# power_5V.net
KiCad netlist of a schematic drawn in Altium Designer
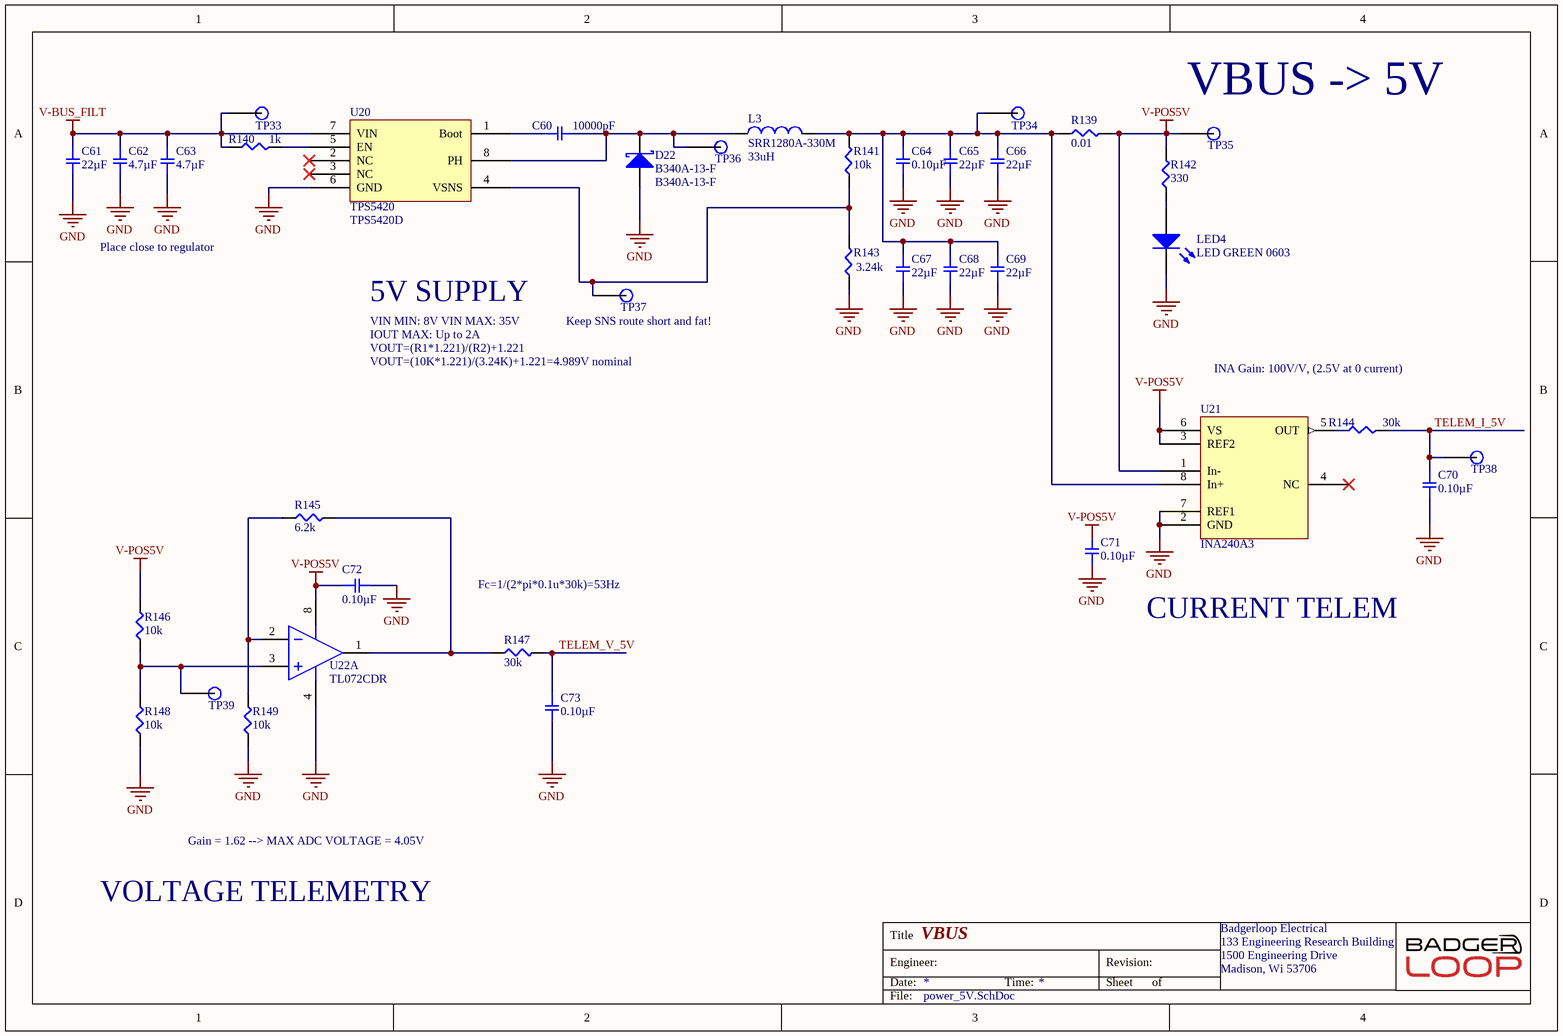
[diagram p0: power_5V.SchDoc]

(export (version "E")
  (design (tool "Eeschema 10.0.6"))
  (components
    (comp (ref "C60")
      (value "10000pF")
      (footprint "SMD-0805C")
      (description "CAP CER 10000PF 250V X7T 0805")
      (fields
        (field (name "DIGI-KEY PART NUMBER") "490-13986-1-ND")
        (field (name "PART NUMBER") "GC321AD72E103KX01D")
      )
      (libsource (lib "capacitors") (part "GC321AD72E103KX01D"))
    )
    (comp (ref "C61")
      (value "22µF")
      (footprint "SMD-1206C")
      (description "CAP CER 22UF 25V X5R 1206")
      (fields
        (field (name "DIGI-KEY PART NUMBER") "490-12451-1-ND")
        (field (name "PART NUMBER") "GRT31CR61E226ME01L")
      )
      (libsource (lib "capacitors") (part "GRT31CR61E226ME01L"))
    )
    (comp (ref "C62")
      (value "4.7µF")
      (footprint "SMD-1206C")
      (description "CAP CER 4.7UF 50V X7S 1206")
      (fields
        (field (name "DIGI-KEY PART NUMBER") "490-11167-1-ND")
        (field (name "PART NUMBER") "GCM31CC71H475KA03L")
      )
      (libsource (lib "capacitors") (part "GCM31CC71H475KA03L"))
    )
    (comp (ref "C63")
      (value "4.7µF")
      (footprint "SMD-1206C")
      (description "CAP CER 4.7UF 50V X7S 1206")
      (fields
        (field (name "DIGI-KEY PART NUMBER") "490-11167-1-ND")
        (field (name "PART NUMBER") "GCM31CC71H475KA03L")
      )
      (libsource (lib "capacitors") (part "GCM31CC71H475KA03L"))
    )
    (comp (ref "C64")
      (value "0.10µF")
      (footprint "SMD-0805C")
      (description "CAP CER 0.1UF 10V U2J 0805")
      (fields
        (field (name "DIGI-KEY PART NUMBER") "490-11592-1-ND")
        (field (name "PART NUMBER") "GRM21B7U1A104JA01L")
      )
      (libsource (lib "capacitors") (part "GRM21B7U1A104JA01L"))
    )
    (comp (ref "C65")
      (value "22µF")
      (footprint "SMD-1206C")
      (description "CAP CER 22UF 25V X5R 1206")
      (fields
        (field (name "DIGI-KEY PART NUMBER") "490-12451-1-ND")
        (field (name "PART NUMBER") "GRT31CR61E226ME01L")
      )
      (libsource (lib "capacitors") (part "GRT31CR61E226ME01L"))
    )
    (comp (ref "C66")
      (value "22µF")
      (footprint "SMD-1206C")
      (description "CAP CER 22UF 25V X5R 1206")
      (fields
        (field (name "DIGI-KEY PART NUMBER") "490-12451-1-ND")
        (field (name "PART NUMBER") "GRT31CR61E226ME01L")
      )
      (libsource (lib "capacitors") (part "GRT31CR61E226ME01L"))
    )
    (comp (ref "C67")
      (value "22µF")
      (footprint "SMD-1206C")
      (description "CAP CER 22UF 25V X5R 1206")
      (fields
        (field (name "DIGI-KEY PART NUMBER") "490-12451-1-ND")
        (field (name "PART NUMBER") "GRT31CR61E226ME01L")
      )
      (libsource (lib "capacitors") (part "GRT31CR61E226ME01L"))
    )
    (comp (ref "C68")
      (value "22µF")
      (footprint "SMD-1206C")
      (description "CAP CER 22UF 25V X5R 1206")
      (fields
        (field (name "DIGI-KEY PART NUMBER") "490-12451-1-ND")
        (field (name "PART NUMBER") "GRT31CR61E226ME01L")
      )
      (libsource (lib "capacitors") (part "GRT31CR61E226ME01L"))
    )
    (comp (ref "C69")
      (value "22µF")
      (footprint "SMD-1206C")
      (description "CAP CER 22UF 25V X5R 1206")
      (fields
        (field (name "DIGI-KEY PART NUMBER") "490-12451-1-ND")
        (field (name "PART NUMBER") "GRT31CR61E226ME01L")
      )
      (libsource (lib "capacitors") (part "GRT31CR61E226ME01L"))
    )
    (comp (ref "C70")
      (value "0.10µF")
      (footprint "SMD-0805C")
      (description "CAP CER 0.1UF 16V X7R 0805")
      (fields
        (field (name "DIGI-KEY PART NUMBER") "490-1683-1-ND")
        (field (name "PART NUMBER") "GRM219R71C104KA01D")
      )
      (libsource (lib "capacitors") (part "GRM219R71C104KA01D"))
    )
    (comp (ref "C71")
      (value "0.10µF")
      (footprint "SMD-0805C")
      (description "CAP CER 0.1UF 10V U2J 0805")
      (fields
        (field (name "DIGI-KEY PART NUMBER") "490-11592-1-ND")
        (field (name "PART NUMBER") "GRM21B7U1A104JA01L")
      )
      (libsource (lib "capacitors") (part "GRM21B7U1A104JA01L"))
    )
    (comp (ref "C72")
      (value "0.10µF")
      (footprint "SMD-0805C")
      (description "CAP CER 0.1UF 10V U2J 0805")
      (fields
        (field (name "DIGI-KEY PART NUMBER") "490-11592-1-ND")
        (field (name "PART NUMBER") "GRM21B7U1A104JA01L")
      )
      (libsource (lib "capacitors") (part "GRM21B7U1A104JA01L"))
    )
    (comp (ref "C73")
      (value "0.10µF")
      (footprint "SMD-0805C")
      (description "CAP CER 0.1UF 16V X7R 0805")
      (fields
        (field (name "DIGI-KEY PART NUMBER") "490-1683-1-ND")
        (field (name "PART NUMBER") "GRM219R71C104KA01D")
      )
      (libsource (lib "capacitors") (part "GRM219R71C104KA01D"))
    )
    (comp (ref "D22")
      (value "B340A-13-F")
      (footprint "DIOM4326X20N")
      (description "DIODE SCHOTTKY 40V 3A SMA")
      (fields
        (field (name "MANUFACTURER") "Diodes")
        (field (name "VOLTAGE") "40V")
        (field (name "MANUFACTURER PART NUMBER") "B340A-13-F")
      )
      (libsource (lib "misc") (part "B340A-13-F"))
    )
    (comp (ref "L3")
      (value "SRR1280A-330M")
      (footprint "INDM120125X75N")
      (description "Inductor Power Shielded Wirewound 33uH 20% 1KHz 28Q-Factor Ferrite 3.5A 57mOhm DCR Automotive T/R")
      (fields
        (field (name "MANUFACTURER") "Bourns")
        (field (name "TOLERANCE") "20%")
        (field (name "INDUCTANCE") "33uH")
      )
      (libsource (lib "misc") (part "SRR1280A-330M"))
    )
    (comp (ref "LED4")
      (value "LED GREEN 0603")
      (footprint "LED 0603 GREEN")
      (fields (field (name "MANUFACTURER") "Lite-On Inc."))
      (libsource (lib "misc") (part "LED GREEN 0603"))
    )
    (comp (ref "R139")
      (value "0.01")
      (footprint "SMD-1206-RES")
      (description "RES SMD 0.01 OHM 1% 1/2W 1206")
      (fields
        (field (name "PART NUMBER") "ERJ-MP2KF10MU")
        (field (name "DIGI-KEY PART NUMBER") "P19322CT-ND")
      )
      (libsource (lib "resistors") (part "ERJ-MP2KF10MU"))
    )
    (comp (ref "R140")
      (value "1k")
      (footprint "SMD-0805-RES")
      (description "RES SMD 1K OHM 5% 1/2W 0805")
      (fields
        (field (name "PART NUMBER") "ERJ-P06J102V")
        (field (name "DIGI-KEY PART NUMBER") "P1.0KADCT-ND")
      )
      (libsource (lib "resistors") (part "ERJ-P06J102V"))
    )
    (comp (ref "R141")
      (value "10k")
      (footprint "SMD-0805-RES")
      (description "RES SMD 10K OHM 5% 1/2W 0805")
      (fields (field (name "PART NUMBER") "ERJ-P06J103V") (field (name "DIGI-KEY PART NUMBER") "P10KADCT-ND"))
      (libsource (lib "resistors") (part "ERJ-P06J103V"))
    )
    (comp (ref "R142")
      (value "330")
      (footprint "SMD-0805-RES")
      (description "RES SMD 330 OHM 5% 1/2W 0805")
      (fields (field (name "PART NUMBER") "ERJ-P06J331V") (field (name "DIGI-KEY PART NUMBER") "P330ADCT-ND"))
      (libsource (lib "resistors") (part "ERJ-P06J331V"))
    )
    (comp (ref "R143")
      (value "3.24k")
      (footprint "SMD-0805-RES")
      (description "RES SMD 3.24K OHM 1% 1/8W 0805")
      (fields
        (field (name "PART NUMBER") "ERJ-6ENF3241V")
        (field (name "DIGI-KEY PART NUMBER") "P3.24KCCT-ND")
      )
      (libsource (lib "resistors") (part "ERJ-6ENF3241V"))
    )
    (comp (ref "R144")
      (value "30k")
      (footprint "SMD-0805-RES")
      (description "RES SMD 30K OHM 1% 1/8W 0805")
      (fields
        (field (name "PART NUMBER") "ERJ-6ENF3002V")
        (field (name "DIGI-KEY PART NUMBER") "P30.0KCCT-ND")
      )
      (libsource (lib "resistors") (part "ERJ-6ENF3002V"))
    )
    (comp (ref "R145")
      (value "6.2k")
      (footprint "SMD-0805-RES")
      (description "RES SMD 6.2K OHM 5% 1/2W 0805")
      (fields
        (field (name "PART NUMBER") "ERJ-P06J622V")
        (field (name "DIGI-KEY PART NUMBER") "P6.2KADCT-ND")
      )
      (libsource (lib "resistors") (part "ERJ-P06J622V"))
    )
    (comp (ref "R146")
      (value "10k")
      (footprint "SMD-0805-RES")
      (description "RES SMD 10K OHM 5% 1/2W 0805")
      (fields (field (name "PART NUMBER") "ERJ-P06J103V") (field (name "DIGI-KEY PART NUMBER") "P10KADCT-ND"))
      (libsource (lib "resistors") (part "ERJ-P06J103V"))
    )
    (comp (ref "R147")
      (value "30k")
      (footprint "SMD-0805-RES")
      (description "RES SMD 30K OHM 5% 1/2W 0805")
      (fields (field (name "PART NUMBER") "ERJ-P06J303V") (field (name "DIGI-KEY PART NUMBER") "P30KADCT-ND"))
      (libsource (lib "resistors") (part "ERJ-P06J303V"))
    )
    (comp (ref "R148")
      (value "10k")
      (footprint "SMD-0805-RES")
      (description "RES SMD 10K OHM 5% 1/2W 0805")
      (fields (field (name "PART NUMBER") "ERJ-P06J103V") (field (name "DIGI-KEY PART NUMBER") "P10KADCT-ND"))
      (libsource (lib "resistors") (part "ERJ-P06J103V"))
    )
    (comp (ref "R149")
      (value "10k")
      (footprint "SMD-0805-RES")
      (description "RES SMD 10K OHM 5% 1/2W 0805")
      (fields (field (name "PART NUMBER") "ERJ-P06J103V") (field (name "DIGI-KEY PART NUMBER") "P10KADCT-ND"))
      (libsource (lib "resistors") (part "ERJ-P06J103V"))
    )
    (comp (ref "TP33")
      (value "TP")
      (footprint "Test Point")
      (description "SMD TEST POINT")
      (libsource (lib "misc") (part "TP"))
    )
    (comp (ref "TP34")
      (value "TP")
      (footprint "Test Point")
      (description "SMD TEST POINT")
      (libsource (lib "misc") (part "TP"))
    )
    (comp (ref "TP35")
      (value "TP")
      (footprint "Test Point")
      (description "SMD TEST POINT")
      (libsource (lib "misc") (part "TP"))
    )
    (comp (ref "TP36")
      (value "TP")
      (footprint "Test Point")
      (description "SMD TEST POINT")
      (libsource (lib "misc") (part "TP"))
    )
    (comp (ref "TP37")
      (value "TP")
      (footprint "Test Point")
      (description "SMD TEST POINT")
      (libsource (lib "misc") (part "TP"))
    )
    (comp (ref "TP38")
      (value "TP")
      (footprint "Test Point")
      (description "SMD TEST POINT")
      (libsource (lib "misc") (part "TP"))
    )
    (comp (ref "TP39")
      (value "TP")
      (footprint "Test Point")
      (description "SMD TEST POINT")
      (libsource (lib "misc") (part "TP"))
    )
    (comp (ref "U20")
      (value "TPS5420")
      (footprint "SOP127P600X175-8N")
      (fields
        (field (name "MANUFACTURER") "Texas Instruments")
        (field (name "MANUFACTURER PART NUMBER") "TPS5420D")
      )
      (libsource (lib "ic") (part "TPS5420"))
    )
    (comp (ref "U21")
      (value "INA240A3")
      (footprint "SOIC127P600X175-8N")
      (description "IC AMP CURRENT SENSE 8-TSSOP 100V/V")
      (fields (field (name "MANUFACTURER") "Texas Instruments"))
      (libsource (lib "ic") (part "INA240A3"))
    )
    (comp (ref "U22")
      (value "TL072CDR")
      (footprint "SOP127P600X175-8N")
      (description "IC OPAMP JFET 3MHZ 8SOIC")
      (fields (field (name "MANUFACTURER") "Texas Instruments"))
      (libsource (lib "ic") (part "TL072CDR"))
    )
  )
  (nets
    (net (code "1") (name "/TELEM_I_5V") (class "Default")
      (node (ref "C70") (pin "1") (pinfunction "1_1") (pintype "passive"))
      (node (ref "R144") (pin "2") (pinfunction "2_2") (pintype "passive"))
      (node (ref "TP38") (pin "1") (pinfunction "1_1") (pintype "passive"))
    )
    (net (code "2") (name "/TELEM_V_5V") (class "Default")
      (node (ref "C73") (pin "1") (pinfunction "1_1") (pintype "passive"))
      (node (ref "R147") (pin "2") (pinfunction "2_2") (pintype "passive"))
    )
    (net (code "3") (name "GND") (class "Default")
      (node (ref "C61") (pin "2") (pinfunction "2_2") (pintype "passive"))
      (node (ref "C62") (pin "2") (pinfunction "2_2") (pintype "passive"))
      (node (ref "C63") (pin "2") (pinfunction "2_2") (pintype "passive"))
      (node (ref "C64") (pin "2") (pinfunction "2_2") (pintype "passive"))
      (node (ref "C65") (pin "2") (pinfunction "2_2") (pintype "passive"))
      (node (ref "C66") (pin "2") (pinfunction "2_2") (pintype "passive"))
      (node (ref "C67") (pin "2") (pinfunction "2_2") (pintype "passive"))
      (node (ref "C68") (pin "2") (pinfunction "2_2") (pintype "passive"))
      (node (ref "C69") (pin "2") (pinfunction "2_2") (pintype "passive"))
      (node (ref "C70") (pin "2") (pinfunction "2_2") (pintype "passive"))
      (node (ref "C71") (pin "1") (pinfunction "1_1") (pintype "passive"))
      (node (ref "C72") (pin "2") (pinfunction "2_2") (pintype "passive"))
      (node (ref "C73") (pin "2") (pinfunction "2_2") (pintype "passive"))
      (node (ref "D22") (pin "1") (pinfunction "A_1") (pintype "passive"))
      (node (ref "LED4") (pin "2") (pinfunction "K_2") (pintype "passive"))
      (node (ref "R143") (pin "1") (pinfunction "1_1") (pintype "passive"))
      (node (ref "R148") (pin "1") (pinfunction "1_1") (pintype "passive"))
      (node (ref "R149") (pin "1") (pinfunction "1_1") (pintype "passive"))
      (node (ref "U20") (pin "6") (pinfunction "GND_6") (pintype "passive"))
      (node (ref "U21") (pin "2") (pinfunction "GND_2") (pintype "power_in"))
      (node (ref "U21") (pin "7") (pinfunction "REF1_7") (pintype "passive"))
      (node (ref "U22") (pin "4") (pinfunction "V-_4") (pintype "power_in"))
    )
    (net (code "4") (name "Net-(D22-K)") (class "Default")
      (node (ref "C60") (pin "2") (pinfunction "2_2") (pintype "passive"))
      (node (ref "D22") (pin "2") (pinfunction "K_2") (pintype "passive"))
      (node (ref "L3") (pin "1") (pinfunction "1_1") (pintype "passive"))
      (node (ref "TP36") (pin "1") (pinfunction "1_1") (pintype "passive"))
      (node (ref "U20") (pin "8") (pinfunction "PH_8") (pintype "passive"))
    )
    (net (code "5") (name "Net-(LED4-A)") (class "Default")
      (node (ref "LED4") (pin "1") (pinfunction "A_1") (pintype "passive"))
      (node (ref "R142") (pin "1") (pinfunction "1_1") (pintype "passive"))
    )
    (net (code "6") (name "Net-(U20-Boot)") (class "Default")
      (node (ref "C60") (pin "1") (pinfunction "1_1") (pintype "passive"))
      (node (ref "U20") (pin "1") (pinfunction "Boot_1") (pintype "passive"))
    )
    (net (code "7") (name "Net-(U20-EN)") (class "Default")
      (node (ref "R140") (pin "2") (pinfunction "2_2") (pintype "passive"))
      (node (ref "U20") (pin "5") (pinfunction "EN_5") (pintype "passive"))
    )
    (net (code "8") (name "Net-(U20-VSNS)") (class "Default")
      (node (ref "R141") (pin "1") (pinfunction "1_1") (pintype "passive"))
      (node (ref "R143") (pin "2") (pinfunction "2_2") (pintype "passive"))
      (node (ref "TP37") (pin "1") (pinfunction "1_1") (pintype "passive"))
      (node (ref "U20") (pin "4") (pinfunction "VSNS_4") (pintype "power_in"))
    )
    (net (code "9") (name "Net-(U21-In+)") (class "Default")
      (node (ref "C64") (pin "1") (pinfunction "1_1") (pintype "passive"))
      (node (ref "C65") (pin "1") (pinfunction "1_1") (pintype "passive"))
      (node (ref "C66") (pin "1") (pinfunction "1_1") (pintype "passive"))
      (node (ref "C67") (pin "1") (pinfunction "1_1") (pintype "passive"))
      (node (ref "C68") (pin "1") (pinfunction "1_1") (pintype "passive"))
      (node (ref "C69") (pin "1") (pinfunction "1_1") (pintype "passive"))
      (node (ref "L3") (pin "2") (pinfunction "2_2") (pintype "passive"))
      (node (ref "R139") (pin "1") (pinfunction "1_1") (pintype "passive"))
      (node (ref "R141") (pin "2") (pinfunction "2_2") (pintype "passive"))
      (node (ref "TP34") (pin "1") (pinfunction "1_1") (pintype "passive"))
      (node (ref "U21") (pin "8") (pinfunction "In+_8") (pintype "passive"))
    )
    (net (code "10") (name "Net-(U21-OUT)") (class "Default")
      (node (ref "R144") (pin "1") (pinfunction "1_1") (pintype "passive"))
      (node (ref "U21") (pin "5") (pinfunction "OUT_5") (pintype "output"))
    )
    (net (code "11") (name "Net-(U22A-IN+)") (class "Default")
      (node (ref "R146") (pin "1") (pinfunction "1_1") (pintype "passive"))
      (node (ref "R148") (pin "2") (pinfunction "2_2") (pintype "passive"))
      (node (ref "TP39") (pin "1") (pinfunction "1_1") (pintype "passive"))
      (node (ref "U22") (pin "3") (pinfunction "IN+_3") (pintype "passive"))
    )
    (net (code "12") (name "Net-(U22A-IN-)") (class "Default")
      (node (ref "R145") (pin "1") (pinfunction "1_1") (pintype "passive"))
      (node (ref "R149") (pin "2") (pinfunction "2_2") (pintype "passive"))
      (node (ref "U22") (pin "2") (pinfunction "IN-_2") (pintype "passive"))
    )
    (net (code "13") (name "Net-(U22A-OUT)") (class "Default")
      (node (ref "R145") (pin "2") (pinfunction "2_2") (pintype "passive"))
      (node (ref "R147") (pin "1") (pinfunction "1_1") (pintype "passive"))
      (node (ref "U22") (pin "1") (pinfunction "OUT_1") (pintype "passive"))
    )
    (net (code "14") (name "V-BUS_FILT") (class "Default")
      (node (ref "C61") (pin "1") (pinfunction "1_1") (pintype "passive"))
      (node (ref "C62") (pin "1") (pinfunction "1_1") (pintype "passive"))
      (node (ref "C63") (pin "1") (pinfunction "1_1") (pintype "passive"))
      (node (ref "R140") (pin "1") (pinfunction "1_1") (pintype "passive"))
      (node (ref "TP33") (pin "1") (pinfunction "1_1") (pintype "passive"))
      (node (ref "U20") (pin "7") (pinfunction "VIN_7") (pintype "passive"))
    )
    (net (code "15") (name "V-POS5V") (class "Default")
      (node (ref "C71") (pin "2") (pinfunction "2_2") (pintype "passive"))
      (node (ref "C72") (pin "1") (pinfunction "1_1") (pintype "passive"))
      (node (ref "R139") (pin "2") (pinfunction "2_2") (pintype "passive"))
      (node (ref "R142") (pin "2") (pinfunction "2_2") (pintype "passive"))
      (node (ref "R146") (pin "2") (pinfunction "2_2") (pintype "passive"))
      (node (ref "TP35") (pin "1") (pinfunction "1_1") (pintype "passive"))
      (node (ref "U21") (pin "1") (pinfunction "In-_1") (pintype "passive"))
      (node (ref "U21") (pin "3") (pinfunction "REF2_3") (pintype "passive"))
      (node (ref "U21") (pin "6") (pinfunction "VS_6") (pintype "power_in"))
      (node (ref "U22") (pin "8") (pinfunction "V+_8") (pintype "power_in"))
    )
    (net (code "16") (name "unconnected-(U20-NC-Pad2)") (class "Default")
      (node (ref "U20") (pin "2") (pinfunction "NC_2") (pintype "power_in+no_connect"))
    )
    (net (code "17") (name "unconnected-(U20-NC-Pad3)") (class "Default")
      (node (ref "U20") (pin "3") (pinfunction "NC_3") (pintype "passive+no_connect"))
    )
    (net (code "18") (name "unconnected-(U21-NC-Pad4)") (class "Default")
      (node (ref "U21") (pin "4") (pinfunction "NC_4") (pintype "passive+no_connect"))
    )
  )
)
